# flyback.net
KiCad netlist of a schematic drawn in Altium Designer
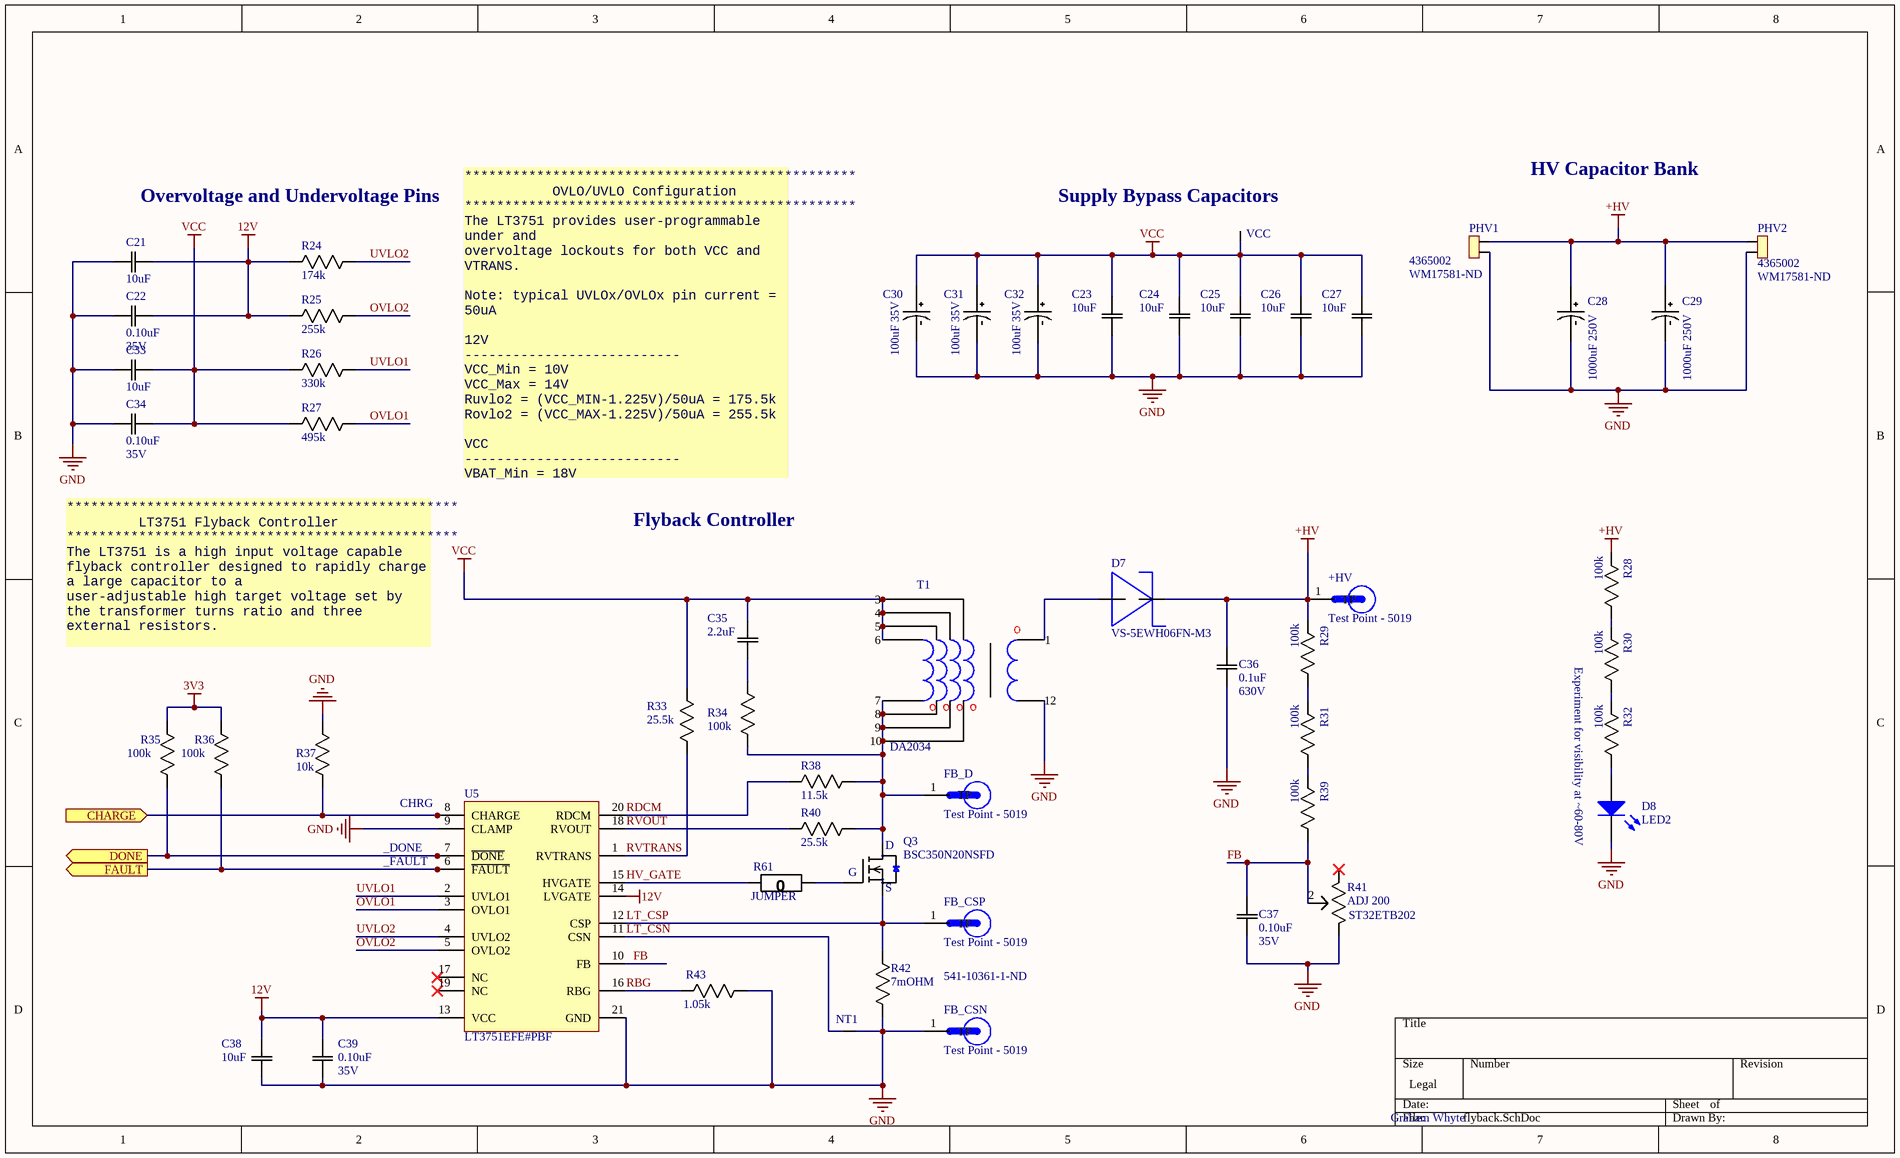
[diagram p0: flyback.SchDoc]

(export (version "E")
  (design (tool "Eeschema 10.0.6"))
  (components
    (comp (ref "+HV")
      (value "Test Point - 5019")
      (footprint "TP380X203")
      (description "PC Test Point, Miniature Phosphor Bronze, Silver Plating Surface Mount Mounting Type")
      (fields (field (name "MP") "5019") (field (name "MF") "Keystone Electronics"))
      (libsource (lib "AltiumLibraries") (part "Test Point - 5019"))
    )
    (comp (ref "C21")
      (value "10uF")
      (footprint "0805")
      (description "CAP CER 10UF 35V X7R 0805")
      (fields (field (name "TOLERANCE") "10%"))
      (libsource (lib "AltiumLibraries") (part "CAP 10uF 35V"))
    )
    (comp (ref "C22")
      (value "0.10uF")
      (footprint "0805")
      (description "CAP CER 0.10UF 35V X7R 0603/0805")
      (fields (field (name "TOLERANCE") "10%") (field (name "RATING") "35V"))
      (libsource (lib "AltiumLibraries") (part "CAP 0.10uF 35V"))
    )
    (comp (ref "C23")
      (value "10uF")
      (footprint "0805")
      (description "CAP CER 10UF 35V X7R 0805")
      (fields (field (name "TOLERANCE") "10%"))
      (libsource (lib "AltiumLibraries") (part "CAP 10uF 35V"))
    )
    (comp (ref "C24")
      (value "10uF")
      (footprint "0805")
      (description "CAP CER 10UF 35V X7R 0805")
      (fields (field (name "TOLERANCE") "10%"))
      (libsource (lib "AltiumLibraries") (part "CAP 10uF 35V"))
    )
    (comp (ref "C25")
      (value "10uF")
      (footprint "0805")
      (description "CAP CER 10UF 35V X7R 0805")
      (fields (field (name "TOLERANCE") "10%"))
      (libsource (lib "AltiumLibraries") (part "CAP 10uF 35V"))
    )
    (comp (ref "C26")
      (value "10uF")
      (footprint "0805")
      (description "CAP CER 10UF 35V X7R 0805")
      (fields (field (name "TOLERANCE") "10%"))
      (libsource (lib "AltiumLibraries") (part "CAP 10uF 35V"))
    )
    (comp (ref "C27")
      (value "10uF")
      (footprint "0805")
      (description "CAP CER 10UF 35V X7R 0805")
      (fields (field (name "TOLERANCE") "10%"))
      (libsource (lib "AltiumLibraries") (part "CAP 10uF 35V"))
    )
    (comp (ref "C28")
      (value "1000uF 250V")
      (footprint "RADIAL, CAN - THRU 25.4mm")
      (description "United Chemi-Con\r\nESMQ251VSN102MQ45S")
      (fields
        (field (name "MANUFACTURER") "United Chemi-Con")
        (field (name "MANUFACTURER PART NUMBER") "ESMQ251VSN102MQ45S")
      )
      (libsource (lib "AltiumLibraries") (part "CAP POL 1000uF"))
    )
    (comp (ref "C29")
      (value "1000uF 250V")
      (footprint "RADIAL, CAN - THRU 25.4mm")
      (description "United Chemi-Con\r\nESMQ251VSN102MQ45S")
      (fields
        (field (name "MANUFACTURER") "United Chemi-Con")
        (field (name "MANUFACTURER PART NUMBER") "ESMQ251VSN102MQ45S")
      )
      (libsource (lib "AltiumLibraries") (part "CAP POL 1000uF"))
    )
    (comp (ref "C30")
      (value "100uF 35V")
      (footprint "CAP POL ALU 6.3x5.8")
      (description "CAP ALUM 100UF 35V SMD")
      (fields (field (name "TOLERANCE") "20%"))
      (libsource (lib "AltiumLibraries") (part "CAP POL 100uF SMD"))
    )
    (comp (ref "C31")
      (value "100uF 35V")
      (footprint "CAP POL ALU 6.3x5.8")
      (description "CAP ALUM 100UF 35V SMD")
      (fields (field (name "TOLERANCE") "20%"))
      (libsource (lib "AltiumLibraries") (part "CAP POL 100uF SMD"))
    )
    (comp (ref "C32")
      (value "100uF 35V")
      (footprint "CAP POL ALU 6.3x5.8")
      (description "CAP ALUM 100UF 35V SMD")
      (fields (field (name "TOLERANCE") "20%"))
      (libsource (lib "AltiumLibraries") (part "CAP POL 100uF SMD"))
    )
    (comp (ref "C33")
      (value "10uF")
      (footprint "0805")
      (description "CAP CER 10UF 35V X7R 0805")
      (fields (field (name "TOLERANCE") "10%"))
      (libsource (lib "AltiumLibraries") (part "CAP 10uF 35V"))
    )
    (comp (ref "C34")
      (value "0.10uF")
      (footprint "0805")
      (description "CAP CER 0.10UF 35V X7R 0603/0805")
      (fields (field (name "TOLERANCE") "10%") (field (name "RATING") "35V"))
      (libsource (lib "AltiumLibraries") (part "CAP 0.10uF 35V"))
    )
    (comp (ref "C35")
      (value "2.2uF")
      (footprint "0805")
      (description "CAP CER 2.2UF 16V X5R 0603/0805")
      (fields (field (name "TOLERANCE") "10%"))
      (libsource (lib "AltiumLibraries") (part "CAP 2.2uF 16V"))
    )
    (comp (ref "C36")
      (value "0.1uF")
      (footprint "1210")
      (description "CAP CER 0.1uF 630V X7R 1210")
      (fields (field (name "TOLERANCE") "10%") (field (name "RATING") "630V"))
      (libsource (lib "AltiumLibraries") (part "CAP 0.1uF 630V"))
    )
    (comp (ref "C37")
      (value "0.10uF")
      (footprint "0805")
      (description "CAP CER 0.10UF 35V X7R 0603/0805")
      (fields (field (name "TOLERANCE") "10%") (field (name "RATING") "35V"))
      (libsource (lib "AltiumLibraries") (part "CAP 0.10uF 35V"))
    )
    (comp (ref "C38")
      (value "10uF")
      (footprint "0805")
      (description "CAP CER 10UF 35V X7R 0805")
      (fields (field (name "TOLERANCE") "10%"))
      (libsource (lib "AltiumLibraries") (part "CAP 10uF 35V"))
    )
    (comp (ref "C39")
      (value "0.10uF")
      (footprint "0805")
      (description "CAP CER 0.10UF 35V X7R 0603/0805")
      (fields (field (name "TOLERANCE") "10%") (field (name "RATING") "35V"))
      (libsource (lib "AltiumLibraries") (part "CAP 0.10uF 35V"))
    )
    (comp (ref "CHRG")
      (value "Test Point (Via)")
      (footprint "TP")
      (libsource (lib "AltiumLibraries") (part "Test Point (Via)"))
    )
    (comp (ref "D7")
      (value "VS-5EWH06FN-M3")
      (footprint "DPAK (TO-252)")
      (description "Diode Switching 600V 5A DPAK")
      (fields (field (name "MF") "Vishay Diodes"))
      (libsource (lib "AltiumLibraries") (part "VS-5EWH06FN-M3"))
    )
    (comp (ref "D8")
      (value "LED2")
      (footprint "3.2X1.6X1.1")
      (description "Typical RED, GREEN, YELLOW, AMBER GaAs LED")
      (libsource (lib "AltiumLibraries") (part "LED GREEN SMD"))
    )
    (comp (ref "FB_CSN")
      (value "Test Point - 5019")
      (footprint "TP380X203")
      (description "PC Test Point, Miniature Phosphor Bronze, Silver Plating Surface Mount Mounting Type")
      (fields (field (name "MP") "5019") (field (name "MF") "Keystone Electronics"))
      (libsource (lib "AltiumLibraries") (part "Test Point - 5019"))
    )
    (comp (ref "FB_CSP")
      (value "Test Point - 5019")
      (footprint "TP380X203")
      (description "PC Test Point, Miniature Phosphor Bronze, Silver Plating Surface Mount Mounting Type")
      (fields (field (name "MP") "5019") (field (name "MF") "Keystone Electronics"))
      (libsource (lib "AltiumLibraries") (part "Test Point - 5019"))
    )
    (comp (ref "FB_D")
      (value "Test Point - 5019")
      (footprint "TP380X203")
      (description "PC Test Point, Miniature Phosphor Bronze, Silver Plating Surface Mount Mounting Type")
      (fields (field (name "MP") "5019") (field (name "MF") "Keystone Electronics"))
      (libsource (lib "AltiumLibraries") (part "Test Point - 5019"))
    )
    (comp (ref "NT1")
      (value "8mil Nettie")
      (footprint "NT_8mil")
      (description "8mil wide nettie")
      (libsource (lib "AltiumLibraries") (part "NT_8"))
    )
    (comp (ref "PHV1")
      (value "4365002")
      (footprint "43650-02")
      (description "MOLEX MICROFIT 2CKT RIGHT THRU")
      (fields
        (field (name "MF") "MOLEX")
        (field (name "MP") "4365002XX")
        (field (name "SUPPLIER PART NUMBER 2") "WM17581-ND")
      )
      (libsource (lib "") (part "CN MOLEX 4365002XX_1"))
    )
    (comp (ref "PHV2")
      (value "4365002")
      (footprint "43650-02")
      (description "MOLEX MICROFIT 2CKT RIGHT THRU")
      (fields
        (field (name "MF") "MOLEX")
        (field (name "MP") "4365002XX")
        (field (name "SUPPLIER PART NUMBER 2") "WM17581-ND")
      )
      (libsource (lib "AltiumLibraries") (part "CN MOLEX 4365002XX"))
    )
    (comp (ref "Q3")
      (value "BSC350N20NSFD")
      (footprint "8-PowerSMD")
      (description "MOSFET N-CH 36A 200V")
      (fields (field (name "MF") "Infineon"))
      (libsource (lib "AltiumLibraries") (part "MOSFET BSC320N20NS3"))
    )
    (comp (ref "R24")
      (value "174k")
      (footprint "0805")
      (description "RES SMD 174K OHM 1% 1/8W 0805")
      (fields
        (field (name "MANUFACTURER") "Yageo")
        (field (name "MANUFACTURER PART NUMBER") "RC0805FR-07174KL")
      )
      (libsource (lib "AltiumLibraries") (part "RES 174k 1/8W"))
    )
    (comp (ref "R25")
      (value "255k")
      (footprint "0805")
      (description "0805 Resistor, 6A, 0.125W, 25ppm, 0.1%, 255K")
      (fields
        (field (name "MANUFACTURER") "Panasonic")
        (field (name "MANUFACTURER PART NUMBER") "ERA-6AEB2553V")
      )
      (libsource (lib "AltiumLibraries") (part "RES 255k 0805"))
    )
    (comp (ref "R26")
      (value "330k")
      (footprint "0805")
      (description "RES SMD 274K OHM 1% 1/8W 0805")
      (libsource (lib "AltiumLibraries") (part "RES 330k 1/8W - 1%"))
    )
    (comp (ref "R27")
      (value "495k")
      (footprint "0805")
      (description "RES SMD 499K OHM 1% 1/8W 0805")
      (fields
        (field (name "MANUFACTURER") "Yageo")
        (field (name "MANUFACTURER PART NUMBER") "RC0805FR-07499KL")
      )
      (libsource (lib "AltiumLibraries") (part "RES 495k 1/8W"))
    )
    (comp (ref "R28")
      (value "100k")
      (footprint "0805")
      (description "RES SMD 100K OHM 5% 1/8W 0805")
      (fields (field (name "TOLERANCE") "5%"))
      (libsource (lib "") (part "RES 100k 1/8W - 5%_1"))
    )
    (comp (ref "R29")
      (value "100k")
      (footprint "0805")
      (description "RES SMD 100K OHM 1% 1/8W 0805")
      (fields (field (name "TOLERANCE") "1%"))
      (libsource (lib "") (part "RES 100k 1/8W - 1%_1"))
    )
    (comp (ref "R30")
      (value "100k")
      (footprint "0805")
      (description "RES SMD 100K OHM 5% 1/8W 0805")
      (fields (field (name "TOLERANCE") "5%"))
      (libsource (lib "AltiumLibraries") (part "RES 100k 1/8W - 5%"))
    )
    (comp (ref "R31")
      (value "100k")
      (footprint "0805")
      (description "RES SMD 100K OHM 1% 1/8W 0805")
      (fields (field (name "TOLERANCE") "1%"))
      (libsource (lib "AltiumLibraries") (part "RES 100k 1/8W - 1%"))
    )
    (comp (ref "R32")
      (value "100k")
      (footprint "0805")
      (description "RES SMD 100K OHM 5% 1/8W 0805")
      (fields (field (name "TOLERANCE") "5%"))
      (libsource (lib "") (part "RES 100k 1/8W - 5%_1"))
    )
    (comp (ref "R33")
      (value "25.5k")
      (footprint "0805")
      (description "RES SMD 25.5K OHM 0.1% 1/8W 0805")
      (fields
        (field (name "MANUFACTURER") "Panasonic")
        (field (name "MANUFACTURER PART NUMBER") "ERA-6AEB2552V")
      )
      (libsource (lib "AltiumLibraries") (part "RES 25.5k 1/8W"))
    )
    (comp (ref "R34")
      (value "100k")
      (footprint "0805")
      (description "RES SMD 100K OHM 1% 1/8W 0805")
      (fields (field (name "TOLERANCE") "1%"))
      (libsource (lib "AltiumLibraries") (part "RES 100k 1/8W - 1%"))
    )
    (comp (ref "R35")
      (value "100k")
      (footprint "0805")
      (description "RES SMD 100K OHM 1% 1/8W 0805")
      (fields (field (name "TOLERANCE") "1%"))
      (libsource (lib "") (part "RES 100k 1/8W - 1%_1"))
    )
    (comp (ref "R36")
      (value "100k")
      (footprint "0805")
      (description "RES SMD 100K OHM 1% 1/8W 0805")
      (fields (field (name "TOLERANCE") "1%"))
      (libsource (lib "AltiumLibraries") (part "RES 100k 1/8W - 1%"))
    )
    (comp (ref "R37")
      (value "10k")
      (footprint "0805")
      (description "RES SMD 10K OHM 1% 1/8W 0805")
      (fields (field (name "TOLERANCE") "1%"))
      (libsource (lib "AltiumLibraries") (part "RES 10k 1/8W - 1%"))
    )
    (comp (ref "R38")
      (value "11.5k")
      (footprint "0805")
      (description "RES SMD 11.5K OHM 0.1% 1/8W 0805 Thin Film")
      (fields
        (field (name "MANUFACTURER") "Panasonic")
        (field (name "MANUFACTURER PART NUMBER") "ERA-6AEB1152V")
      )
      (libsource (lib "AltiumLibraries") (part "RES 11.5k 1/8W"))
    )
    (comp (ref "R39")
      (value "100k")
      (footprint "0805")
      (description "RES SMD 100K OHM 1% 1/8W 0805")
      (fields (field (name "TOLERANCE") "1%"))
      (libsource (lib "") (part "RES 100k 1/8W - 1%_1"))
    )
    (comp (ref "R40")
      (value "25.5k")
      (footprint "0805")
      (description "RES SMD 25.5K OHM 0.1% 1/8W 0805")
      (fields
        (field (name "MANUFACTURER") "Panasonic")
        (field (name "MANUFACTURER PART NUMBER") "ERA-6AEB2552V")
      )
      (libsource (lib "AltiumLibraries") (part "RES 25.5k 1/8W"))
    )
    (comp (ref "R41")
      (value "ADJ 200")
      (footprint "POT SMD")
      (description "SMD Potentiometer 200Ohm Range")
      (libsource (lib "AltiumLibraries") (part "RES POT 200"))
    )
    (comp (ref "R42")
      (value "7mOHM")
      (footprint "2512")
      (description "RES SMD 7m OHM 1% 3W 2512")
      (fields
        (field (name "TOLERANCE") "1%")
        (field (name "MFG") "VISHAY")
        (field (name "SUPPLIER PART NUMBER 1") "541-10361-1-ND")
      )
      (libsource (lib "AltiumLibraries") (part "RES 7m 3W"))
    )
    (comp (ref "R43")
      (value "1.05k")
      (footprint "0805")
      (description "RES SMD 1.05K OHM 0.1% 1/8W 0805")
      (fields (field (name "TOLERANCE") "0.1%"))
      (libsource (lib "AltiumLibraries") (part "RES 1.05k 1/8W"))
    )
    (comp (ref "R61")
      (value "JUMPER")
      (footprint "0805")
      (description "RES SMD 0 OHM JUMPER GENERIC 0805")
      (libsource (lib "AltiumLibraries") (part "RES 0 JUMPER"))
    )
    (comp (ref "T1")
      (value "DA2034")
      (footprint "DA2034")
      (description "Audio Transformers / Signal Transformers DA2032 Cap Chrgr For Linear LT3750/51")
      (libsource (lib "AltiumLibraries") (part "DA2034"))
    )
    (comp (ref "U5")
      (value "LT3751EFE#PBF")
      (footprint "LT-FE-20-EPV-CB_L")
      (description "Controller to 20-Pin TSSOP EP")
      (fields (field (name "MANUFACTURER") "Analog Devices / Linear Technology"))
      (libsource (lib "AltiumLibraries") (part "LT3751EFE#PBF"))
    )
    (comp (ref "VCC")
      (value "Test Point (Via)")
      (footprint "TP")
      (libsource (lib "AltiumLibraries") (part "Test Point (Via)"))
    )
    (comp (ref "_DONE")
      (value "Test Point (Via)")
      (footprint "TP")
      (libsource (lib "AltiumLibraries") (part "Test Point (Via)"))
    )
    (comp (ref "_FAULT")
      (value "Test Point (Via)")
      (footprint "TP")
      (libsource (lib "AltiumLibraries") (part "Test Point (Via)"))
    )
  )
  (nets
    (net (code "1") (name "+HV") (class "Default")
      (node (ref "+HV") (pin "1") (pinfunction "TP_1") (pintype "passive"))
      (node (ref "C28") (pin "POS") (pinfunction "POS_POS") (pintype "passive"))
      (node (ref "C29") (pin "POS") (pinfunction "POS_POS") (pintype "passive"))
      (node (ref "C36") (pin "1") (pinfunction "C1_1") (pintype "passive"))
      (node (ref "D7") (pin "OUT") (pinfunction "OUT_OUT") (pintype "passive"))
      (node (ref "PHV1") (pin "2") (pinfunction "2_2") (pintype "passive"))
      (node (ref "PHV2") (pin "2") (pinfunction "2_2") (pintype "passive"))
      (node (ref "R28") (pin "2") (pinfunction "R2_2") (pintype "passive"))
      (node (ref "R29") (pin "2") (pinfunction "R2_2") (pintype "passive"))
    )
    (net (code "3") (name "/CHARGE") (class "Default")
      (node (ref "CHRG") (pin "1") (pinfunction "1_1") (pintype "passive"))
      (node (ref "R37") (pin "2") (pinfunction "R2_2") (pintype "passive"))
      (node (ref "U5") (pin "8") (pinfunction "CHARGE_8") (pintype "passive"))
    )
    (net (code "4") (name "/DONE") (class "Default")
      (node (ref "R35") (pin "1") (pinfunction "R1_1") (pintype "passive"))
      (node (ref "U5") (pin "7") (pinfunction "~{DONE}_7") (pintype "passive"))
      (node (ref "_DONE") (pin "1") (pinfunction "1_1") (pintype "passive"))
    )
    (net (code "5") (name "/FAULT") (class "Default")
      (node (ref "R36") (pin "1") (pinfunction "R1_1") (pintype "passive"))
      (node (ref "U5") (pin "6") (pinfunction "~{FAULT}_6") (pintype "passive"))
      (node (ref "_FAULT") (pin "1") (pinfunction "1_1") (pintype "passive"))
    )
    (net (code "6") (name "/FB") (class "Default")
      (node (ref "C37") (pin "1") (pinfunction "C1_1") (pintype "passive"))
      (node (ref "R39") (pin "1") (pinfunction "R1_1") (pintype "passive"))
      (node (ref "R41") (pin "2") (pinfunction "2_2") (pintype "passive"))
      (node (ref "U5") (pin "10") (pinfunction "FB_10") (pintype "passive"))
    )
    (net (code "7") (name "/HV_GATE") (class "Default")
      (node (ref "R61") (pin "2") (pinfunction "R2_2") (pintype "passive"))
      (node (ref "U5") (pin "15") (pinfunction "HVGATE_15") (pintype "passive"))
    )
    (net (code "8") (name "/LT_CSN") (class "Default")
      (node (ref "NT1") (pin "1") (pinfunction "1_1") (pintype "passive"))
      (node (ref "U5") (pin "11") (pinfunction "CSN_11") (pintype "passive"))
    )
    (net (code "9") (name "/LT_CSP") (class "Default")
      (node (ref "FB_CSP") (pin "1") (pinfunction "TP_1") (pintype "passive"))
      (node (ref "Q3") (pin "S") (pinfunction "S_S") (pintype "passive"))
      (node (ref "R42") (pin "2") (pinfunction "R2_2") (pintype "passive"))
      (node (ref "U5") (pin "12") (pinfunction "CSP_12") (pintype "passive"))
    )
    (net (code "10") (name "/OVLO1") (class "Default")
      (node (ref "R27") (pin "1") (pinfunction "R1_1") (pintype "passive"))
      (node (ref "U5") (pin "3") (pinfunction "OVLO1_3") (pintype "passive"))
    )
    (net (code "11") (name "/OVLO2") (class "Default")
      (node (ref "R25") (pin "1") (pinfunction "R1_1") (pintype "passive"))
      (node (ref "U5") (pin "5") (pinfunction "OVLO2_5") (pintype "passive"))
    )
    (net (code "12") (name "/RBG") (class "Default")
      (node (ref "R43") (pin "2") (pinfunction "R2_2") (pintype "passive"))
      (node (ref "U5") (pin "16") (pinfunction "RBG_16") (pintype "passive"))
    )
    (net (code "13") (name "/RDCM") (class "Default")
      (node (ref "R38") (pin "2") (pinfunction "R2_2") (pintype "passive"))
      (node (ref "U5") (pin "20") (pinfunction "RDCM_20") (pintype "passive"))
    )
    (net (code "14") (name "/RVOUT") (class "Default")
      (node (ref "R40") (pin "2") (pinfunction "R2_2") (pintype "passive"))
      (node (ref "U5") (pin "18") (pinfunction "RVOUT_18") (pintype "passive"))
    )
    (net (code "15") (name "/RVTRANS") (class "Default")
      (node (ref "R33") (pin "2") (pinfunction "R2_2") (pintype "passive"))
      (node (ref "U5") (pin "1") (pinfunction "RVTRANS_1") (pintype "passive"))
    )
    (net (code "16") (name "/UVLO1") (class "Default")
      (node (ref "R26") (pin "1") (pinfunction "R1_1") (pintype "passive"))
      (node (ref "U5") (pin "2") (pinfunction "UVLO1_2") (pintype "passive"))
    )
    (net (code "17") (name "/UVLO2") (class "Default")
      (node (ref "R24") (pin "1") (pinfunction "R1_1") (pintype "passive"))
      (node (ref "U5") (pin "4") (pinfunction "UVLO2_4") (pintype "passive"))
    )
    (net (code "18") (name "3V3") (class "Default")
      (node (ref "R35") (pin "2") (pinfunction "R2_2") (pintype "passive"))
      (node (ref "R36") (pin "2") (pinfunction "R2_2") (pintype "passive"))
    )
    (net (code "19") (name "12V") (class "Default")
      (node (ref "C21") (pin "2") (pinfunction "C2_2") (pintype "passive"))
      (node (ref "C22") (pin "2") (pinfunction "C2_2") (pintype "passive"))
      (node (ref "C38") (pin "1") (pinfunction "C1_1") (pintype "passive"))
      (node (ref "C39") (pin "1") (pinfunction "C1_1") (pintype "passive"))
      (node (ref "R24") (pin "2") (pinfunction "R2_2") (pintype "passive"))
      (node (ref "R25") (pin "2") (pinfunction "R2_2") (pintype "passive"))
      (node (ref "U5") (pin "13") (pinfunction "VCC_13") (pintype "passive"))
      (node (ref "U5") (pin "14") (pinfunction "LVGATE_14") (pintype "passive"))
    )
    (net (code "20") (name "GND") (class "Default")
      (node (ref "C21") (pin "1") (pinfunction "C1_1") (pintype "passive"))
      (node (ref "C22") (pin "1") (pinfunction "C1_1") (pintype "passive"))
      (node (ref "C23") (pin "1") (pinfunction "C1_1") (pintype "passive"))
      (node (ref "C24") (pin "1") (pinfunction "C1_1") (pintype "passive"))
      (node (ref "C25") (pin "1") (pinfunction "C1_1") (pintype "passive"))
      (node (ref "C26") (pin "1") (pinfunction "C1_1") (pintype "passive"))
      (node (ref "C27") (pin "1") (pinfunction "C1_1") (pintype "passive"))
      (node (ref "C28") (pin "NEG") (pinfunction "NEG_NEG") (pintype "passive"))
      (node (ref "C29") (pin "NEG") (pinfunction "NEG_NEG") (pintype "passive"))
      (node (ref "C30") (pin "NEG") (pinfunction "NEG_NEG") (pintype "passive"))
      (node (ref "C31") (pin "NEG") (pinfunction "NEG_NEG") (pintype "passive"))
      (node (ref "C32") (pin "NEG") (pinfunction "NEG_NEG") (pintype "passive"))
      (node (ref "C33") (pin "1") (pinfunction "C1_1") (pintype "passive"))
      (node (ref "C34") (pin "1") (pinfunction "C1_1") (pintype "passive"))
      (node (ref "C36") (pin "2") (pinfunction "C2_2") (pintype "passive"))
      (node (ref "C37") (pin "2") (pinfunction "C2_2") (pintype "passive"))
      (node (ref "C38") (pin "2") (pinfunction "C2_2") (pintype "passive"))
      (node (ref "C39") (pin "2") (pinfunction "C2_2") (pintype "passive"))
      (node (ref "D8") (pin "2") (pinfunction "K_2") (pintype "passive"))
      (node (ref "FB_CSN") (pin "1") (pinfunction "TP_1") (pintype "passive"))
      (node (ref "NT1") (pin "2") (pinfunction "2_2") (pintype "passive"))
      (node (ref "PHV1") (pin "1") (pinfunction "1_1") (pintype "passive"))
      (node (ref "PHV2") (pin "1") (pinfunction "1_1") (pintype "passive"))
      (node (ref "R37") (pin "1") (pinfunction "R1_1") (pintype "passive"))
      (node (ref "R41") (pin "3") (pinfunction "3_3") (pintype "passive"))
      (node (ref "R42") (pin "1") (pinfunction "R1_1") (pintype "passive"))
      (node (ref "R43") (pin "1") (pinfunction "R1_1") (pintype "passive"))
      (node (ref "T1") (pin "12") (pinfunction "12_12") (pintype "passive"))
      (node (ref "U5") (pin "21") (pinfunction "GND_21") (pintype "passive"))
      (node (ref "U5") (pin "9") (pinfunction "CLAMP_9") (pintype "passive"))
    )
    (net (code "21") (name "Net-(C35-C1)") (class "Default")
      (node (ref "C35") (pin "1") (pinfunction "C1_1") (pintype "passive"))
      (node (ref "R34") (pin "1") (pinfunction "R1_1") (pintype "passive"))
    )
    (net (code "22") (name "Net-(D7-PadIN)") (class "Default")
      (node (ref "D7") (pin "IN") (pinfunction "IN_IN") (pintype "passive"))
      (node (ref "T1") (pin "1") (pinfunction "1_1") (pintype "passive"))
    )
    (net (code "23") (name "Net-(D8-A)") (class "Default")
      (node (ref "D8") (pin "1") (pinfunction "A_1") (pintype "passive"))
      (node (ref "R32") (pin "1") (pinfunction "R1_1") (pintype "passive"))
    )
    (net (code "24") (name "Net-(FB_D-TP)") (class "Default")
      (node (ref "FB_D") (pin "1") (pinfunction "TP_1") (pintype "passive"))
      (node (ref "Q3") (pin "D") (pinfunction "D_D") (pintype "passive"))
      (node (ref "R34") (pin "2") (pinfunction "R2_2") (pintype "passive"))
      (node (ref "R38") (pin "1") (pinfunction "R1_1") (pintype "passive"))
      (node (ref "R40") (pin "1") (pinfunction "R1_1") (pintype "passive"))
      (node (ref "T1") (pin "10") (pinfunction "10_10") (pintype "passive"))
      (node (ref "T1") (pin "7") (pinfunction "7_7") (pintype "passive"))
      (node (ref "T1") (pin "8") (pinfunction "8_8") (pintype "passive"))
      (node (ref "T1") (pin "9") (pinfunction "9_9") (pintype "passive"))
    )
    (net (code "25") (name "Net-(R28-R1)") (class "Default")
      (node (ref "R28") (pin "1") (pinfunction "R1_1") (pintype "passive"))
      (node (ref "R30") (pin "2") (pinfunction "R2_2") (pintype "passive"))
    )
    (net (code "26") (name "Net-(R29-R1)") (class "Default")
      (node (ref "R29") (pin "1") (pinfunction "R1_1") (pintype "passive"))
      (node (ref "R31") (pin "2") (pinfunction "R2_2") (pintype "passive"))
    )
    (net (code "27") (name "Net-(R30-R1)") (class "Default")
      (node (ref "R30") (pin "1") (pinfunction "R1_1") (pintype "passive"))
      (node (ref "R32") (pin "2") (pinfunction "R2_2") (pintype "passive"))
    )
    (net (code "28") (name "Net-(R31-R1)") (class "Default")
      (node (ref "R31") (pin "1") (pinfunction "R1_1") (pintype "passive"))
      (node (ref "R39") (pin "2") (pinfunction "R2_2") (pintype "passive"))
    )
    (net (code "29") (name "Net-(R61-R1)") (class "Default")
      (node (ref "Q3") (pin "G") (pinfunction "G_G") (pintype "passive"))
      (node (ref "R61") (pin "1") (pinfunction "R1_1") (pintype "passive"))
    )
    (net (code "30") (name "VCC") (class "Default")
      (node (ref "C23") (pin "2") (pinfunction "C2_2") (pintype "passive"))
      (node (ref "C24") (pin "2") (pinfunction "C2_2") (pintype "passive"))
      (node (ref "C25") (pin "2") (pinfunction "C2_2") (pintype "passive"))
      (node (ref "C26") (pin "2") (pinfunction "C2_2") (pintype "passive"))
      (node (ref "C27") (pin "2") (pinfunction "C2_2") (pintype "passive"))
      (node (ref "C30") (pin "POS") (pinfunction "POS_POS") (pintype "passive"))
      (node (ref "C31") (pin "POS") (pinfunction "POS_POS") (pintype "passive"))
      (node (ref "C32") (pin "POS") (pinfunction "POS_POS") (pintype "passive"))
      (node (ref "C33") (pin "2") (pinfunction "C2_2") (pintype "passive"))
      (node (ref "C34") (pin "2") (pinfunction "C2_2") (pintype "passive"))
      (node (ref "C35") (pin "2") (pinfunction "C2_2") (pintype "passive"))
      (node (ref "R26") (pin "2") (pinfunction "R2_2") (pintype "passive"))
      (node (ref "R27") (pin "2") (pinfunction "R2_2") (pintype "passive"))
      (node (ref "R33") (pin "1") (pinfunction "R1_1") (pintype "passive"))
      (node (ref "T1") (pin "3") (pinfunction "3_3") (pintype "passive"))
      (node (ref "T1") (pin "4") (pinfunction "4_4") (pintype "passive"))
      (node (ref "T1") (pin "5") (pinfunction "5_5") (pintype "passive"))
      (node (ref "T1") (pin "6") (pinfunction "6_6") (pintype "passive"))
      (node (ref "VCC") (pin "1") (pinfunction "1_1") (pintype "passive"))
    )
    (net (code "31") (name "unconnected-(R41-Pad1)") (class "Default")
      (node (ref "R41") (pin "1") (pinfunction "1_1") (pintype "passive+no_connect"))
    )
    (net (code "32") (name "unconnected-(U5-NC-Pad17)") (class "Default")
      (node (ref "U5") (pin "17") (pinfunction "NC_17") (pintype "passive+no_connect"))
    )
    (net (code "33") (name "unconnected-(U5-NC-Pad19)") (class "Default")
      (node (ref "U5") (pin "19") (pinfunction "NC_19") (pintype "passive+no_connect"))
    )
  )
)
